# ahmed23shaf_AMRadioReceiver__PCB__Sheet_.net
KiCad netlist of a schematic drawn in Altium Designer
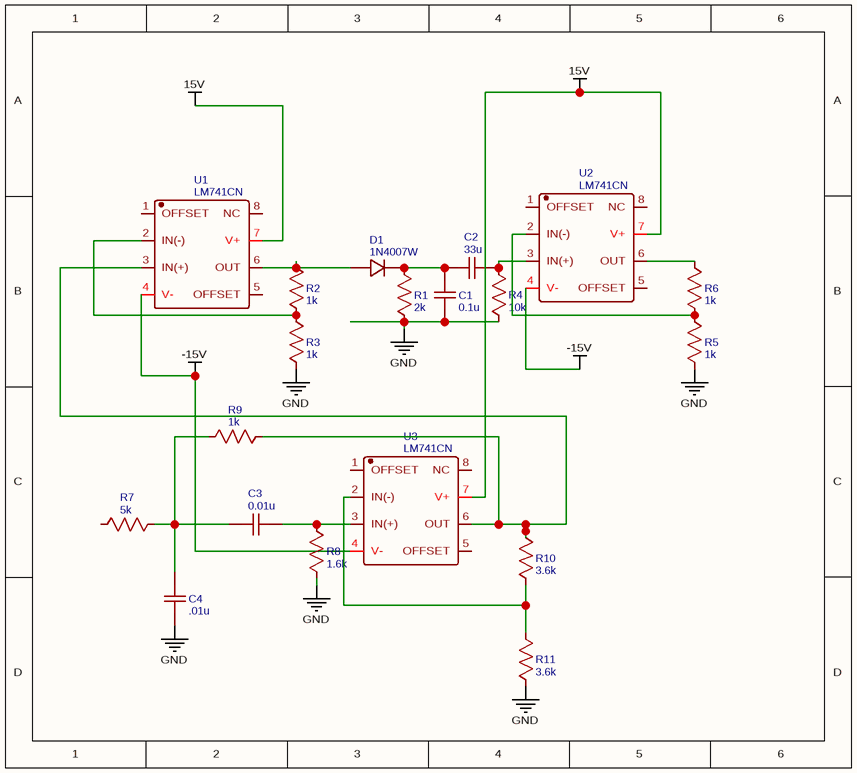
[diagram p0: ahmed23shaf_AMRadioReceiver__PCB__Sheet_1_2023-12-17.schdoc]

(export (version "E")
  (design (tool "Eeschema 10.0.6"))
  (components
    (comp (ref "C1")
      (value "0.1u")
      (fields (field (name "CONTRIBUTOR") "LCEDA_Lib"))
      (libsource (lib "altium-import") (part "root_1_0.1u_"))
    )
    (comp (ref "C2")
      (value "33u")
      (fields (field (name "CONTRIBUTOR") "LCEDA_Lib"))
      (libsource (lib "altium-import") (part "root_0_33u_"))
    )
    (comp (ref "C3")
      (value "0.01u")
      (fields (field (name "CONTRIBUTOR") "LCEDA_Lib"))
      (libsource (lib "altium-import") (part "root_0_0.01u_"))
    )
    (comp (ref "C4")
      (value ".01u")
      (fields (field (name "CONTRIBUTOR") "LCEDA_Lib"))
      (libsource (lib "altium-import") (part "root_1_.01u_"))
    )
    (comp (ref "D1")
      (value "1N4007W")
      (fields (field (name "MANUFACTURER") "BLUE ROCKET") (field (name "CONTRIBUTOR") "LCEDA_Lib"))
      (libsource (lib "altium-import") (part "root_0_1N4007W_"))
    )
    (comp (ref "R1")
      (value "2k")
      (fields (field (name "CONTRIBUTOR") "LCEDA_Lib"))
      (libsource (lib "altium-import") (part "root_1_2k_"))
    )
    (comp (ref "R2")
      (value "1k")
      (fields (field (name "CONTRIBUTOR") "LCEDA_Lib"))
      (libsource (lib "altium-import") (part "root_1_1k_"))
    )
    (comp (ref "R3")
      (value "1k")
      (fields (field (name "CONTRIBUTOR") "LCEDA_Lib"))
      (libsource (lib "altium-import") (part "root_1_1k_"))
    )
    (comp (ref "R4")
      (value "10k")
      (fields (field (name "CONTRIBUTOR") "LCEDA_Lib"))
      (libsource (lib "altium-import") (part "root_1_10k_"))
    )
    (comp (ref "R5")
      (value "1k")
      (fields (field (name "CONTRIBUTOR") "LCEDA_Lib"))
      (libsource (lib "altium-import") (part "root_1_1k_"))
    )
    (comp (ref "R6")
      (value "1k")
      (fields (field (name "CONTRIBUTOR") "LCEDA_Lib"))
      (libsource (lib "altium-import") (part "root_1_1k_"))
    )
    (comp (ref "R7")
      (value "5k")
      (fields (field (name "CONTRIBUTOR") "LCEDA_Lib"))
      (libsource (lib "altium-import") (part "root_0_5k_"))
    )
    (comp (ref "R8")
      (value "1.6k")
      (fields (field (name "CONTRIBUTOR") "LCEDA_Lib"))
      (libsource (lib "altium-import") (part "root_1_1.6k_"))
    )
    (comp (ref "R9")
      (value "1k")
      (fields (field (name "CONTRIBUTOR") "LCEDA_Lib"))
      (libsource (lib "altium-import") (part "root_0_1k_"))
    )
    (comp (ref "R10")
      (value "3.6k")
      (fields (field (name "CONTRIBUTOR") "LCEDA_Lib"))
      (libsource (lib "altium-import") (part "root_1_3.6k_"))
    )
    (comp (ref "R11")
      (value "3.6k")
      (fields (field (name "CONTRIBUTOR") "LCEDA_Lib"))
      (libsource (lib "altium-import") (part "root_1_3.6k_"))
    )
    (comp (ref "U1")
      (value "LM741CN")
      (fields (field (name "MANUFACTURER") "TI(德州仪器)") (field (name "MANUFACTURER PART") "LM741CN/NOPB"))
      (libsource (lib "altium-import") (part "root_0_LM741CN_"))
    )
    (comp (ref "U2")
      (value "LM741CN")
      (fields (field (name "MANUFACTURER") "TI(德州仪器)") (field (name "MANUFACTURER PART") "LM741CN/NOPB"))
      (libsource (lib "altium-import") (part "root_0_LM741CN_"))
    )
    (comp (ref "U3")
      (value "LM741CN")
      (fields (field (name "MANUFACTURER") "TI(德州仪器)") (field (name "MANUFACTURER PART") "LM741CN/NOPB"))
      (libsource (lib "altium-import") (part "root_0_LM741CN_"))
    )
  )
  (nets
    (net (code "1") (name "-15V") (class "Default")
      (node (ref "U1") (pin "4") (pinfunction "V-_4") (pintype "passive"))
      (node (ref "U2") (pin "4") (pinfunction "V-_4") (pintype "passive"))
      (node (ref "U3") (pin "4") (pinfunction "V-_4") (pintype "passive"))
    )
    (net (code "2") (name "15V") (class "Default")
      (node (ref "U1") (pin "7") (pinfunction "V+_7") (pintype "passive"))
      (node (ref "U2") (pin "7") (pinfunction "V+_7") (pintype "passive"))
      (node (ref "U3") (pin "7") (pinfunction "V+_7") (pintype "passive"))
    )
    (net (code "3") (name "GND") (class "Default")
      (node (ref "C1") (pin "1") (pinfunction "1_1") (pintype "passive"))
      (node (ref "C4") (pin "1") (pinfunction "1_1") (pintype "passive"))
      (node (ref "R1") (pin "1") (pinfunction "1_1") (pintype "passive"))
      (node (ref "R11") (pin "1") (pinfunction "1_1") (pintype "passive"))
      (node (ref "R3") (pin "1") (pinfunction "1_1") (pintype "passive"))
      (node (ref "R4") (pin "1") (pinfunction "1_1") (pintype "passive"))
      (node (ref "R5") (pin "1") (pinfunction "1_1") (pintype "passive"))
      (node (ref "R8") (pin "1") (pinfunction "1_1") (pintype "passive"))
    )
    (net (code "4") (name "Net-(C1-Pad2)") (class "Default")
      (node (ref "C1") (pin "2") (pinfunction "2_2") (pintype "passive"))
      (node (ref "C2") (pin "1") (pinfunction "1_1") (pintype "passive"))
      (node (ref "D1") (pin "1") (pinfunction "1_1") (pintype "passive"))
      (node (ref "R1") (pin "2") (pinfunction "2_2") (pintype "passive"))
    )
    (net (code "5") (name "Net-(C3-Pad1)") (class "Default")
      (node (ref "C3") (pin "1") (pinfunction "1_1") (pintype "passive"))
      (node (ref "C4") (pin "2") (pinfunction "2_2") (pintype "passive"))
      (node (ref "R7") (pin "2") (pinfunction "2_2") (pintype "passive"))
      (node (ref "R9") (pin "1") (pinfunction "1_1") (pintype "passive"))
    )
    (net (code "6") (name "Net-(U1-IN(+))") (class "Default")
      (node (ref "R10") (pin "2") (pinfunction "2_2") (pintype "passive"))
      (node (ref "R9") (pin "2") (pinfunction "2_2") (pintype "passive"))
      (node (ref "U1") (pin "3") (pinfunction "IN(+)_3") (pintype "passive"))
      (node (ref "U3") (pin "6") (pinfunction "OUT_6") (pintype "passive"))
    )
    (net (code "7") (name "Net-(U1-IN(-))") (class "Default")
      (node (ref "R2") (pin "1") (pinfunction "1_1") (pintype "passive"))
      (node (ref "R3") (pin "2") (pinfunction "2_2") (pintype "passive"))
      (node (ref "U1") (pin "2") (pinfunction "IN(-)_2") (pintype "passive"))
    )
    (net (code "8") (name "Net-(U1-OUT)") (class "Default")
      (node (ref "D1") (pin "2") (pinfunction "2_2") (pintype "passive"))
      (node (ref "R2") (pin "2") (pinfunction "2_2") (pintype "passive"))
      (node (ref "U1") (pin "6") (pinfunction "OUT_6") (pintype "passive"))
    )
    (net (code "9") (name "Net-(U2-IN(+))") (class "Default")
      (node (ref "C2") (pin "2") (pinfunction "2_2") (pintype "passive"))
      (node (ref "R4") (pin "2") (pinfunction "2_2") (pintype "passive"))
      (node (ref "U2") (pin "3") (pinfunction "IN(+)_3") (pintype "passive"))
    )
    (net (code "10") (name "Net-(U2-IN(-))") (class "Default")
      (node (ref "R5") (pin "2") (pinfunction "2_2") (pintype "passive"))
      (node (ref "R6") (pin "1") (pinfunction "1_1") (pintype "passive"))
      (node (ref "U2") (pin "2") (pinfunction "IN(-)_2") (pintype "passive"))
    )
    (net (code "11") (name "Net-(U2-OUT)") (class "Default")
      (node (ref "R6") (pin "2") (pinfunction "2_2") (pintype "passive"))
      (node (ref "U2") (pin "6") (pinfunction "OUT_6") (pintype "passive"))
    )
    (net (code "12") (name "Net-(U3-IN(+))") (class "Default")
      (node (ref "C3") (pin "2") (pinfunction "2_2") (pintype "passive"))
      (node (ref "R8") (pin "2") (pinfunction "2_2") (pintype "passive"))
      (node (ref "U3") (pin "3") (pinfunction "IN(+)_3") (pintype "passive"))
    )
    (net (code "13") (name "Net-(U3-IN(-))") (class "Default")
      (node (ref "R10") (pin "1") (pinfunction "1_1") (pintype "passive"))
      (node (ref "R11") (pin "2") (pinfunction "2_2") (pintype "passive"))
      (node (ref "U3") (pin "2") (pinfunction "IN(-)_2") (pintype "passive"))
    )
    (net (code "14") (name "unconnected-(R7-Pad1)") (class "Default")
      (node (ref "R7") (pin "1") (pinfunction "1_1") (pintype "passive"))
    )
    (net (code "15") (name "unconnected-(U1-NC-Pad8)") (class "Default")
      (node (ref "U1") (pin "8") (pinfunction "NC_8") (pintype "passive"))
    )
    (net (code "16") (name "unconnected-(U1-OFFSET-Pad1)") (class "Default")
      (node (ref "U1") (pin "1") (pinfunction "OFFSET_1") (pintype "passive"))
    )
    (net (code "17") (name "unconnected-(U1-OFFSET-Pad5)") (class "Default")
      (node (ref "U1") (pin "5") (pinfunction "OFFSET_5") (pintype "passive"))
    )
    (net (code "18") (name "unconnected-(U2-NC-Pad8)") (class "Default")
      (node (ref "U2") (pin "8") (pinfunction "NC_8") (pintype "passive"))
    )
    (net (code "19") (name "unconnected-(U2-OFFSET-Pad1)") (class "Default")
      (node (ref "U2") (pin "1") (pinfunction "OFFSET_1") (pintype "passive"))
    )
    (net (code "20") (name "unconnected-(U2-OFFSET-Pad5)") (class "Default")
      (node (ref "U2") (pin "5") (pinfunction "OFFSET_5") (pintype "passive"))
    )
    (net (code "21") (name "unconnected-(U3-NC-Pad8)") (class "Default")
      (node (ref "U3") (pin "8") (pinfunction "NC_8") (pintype "passive"))
    )
    (net (code "22") (name "unconnected-(U3-OFFSET-Pad1)") (class "Default")
      (node (ref "U3") (pin "1") (pinfunction "OFFSET_1") (pintype "passive"))
    )
    (net (code "23") (name "unconnected-(U3-OFFSET-Pad5)") (class "Default")
      (node (ref "U3") (pin "5") (pinfunction "OFFSET_5") (pintype "passive"))
    )
  )
)
